# 09_MCU.net
KiCad netlist of a schematic drawn in Altium Designer
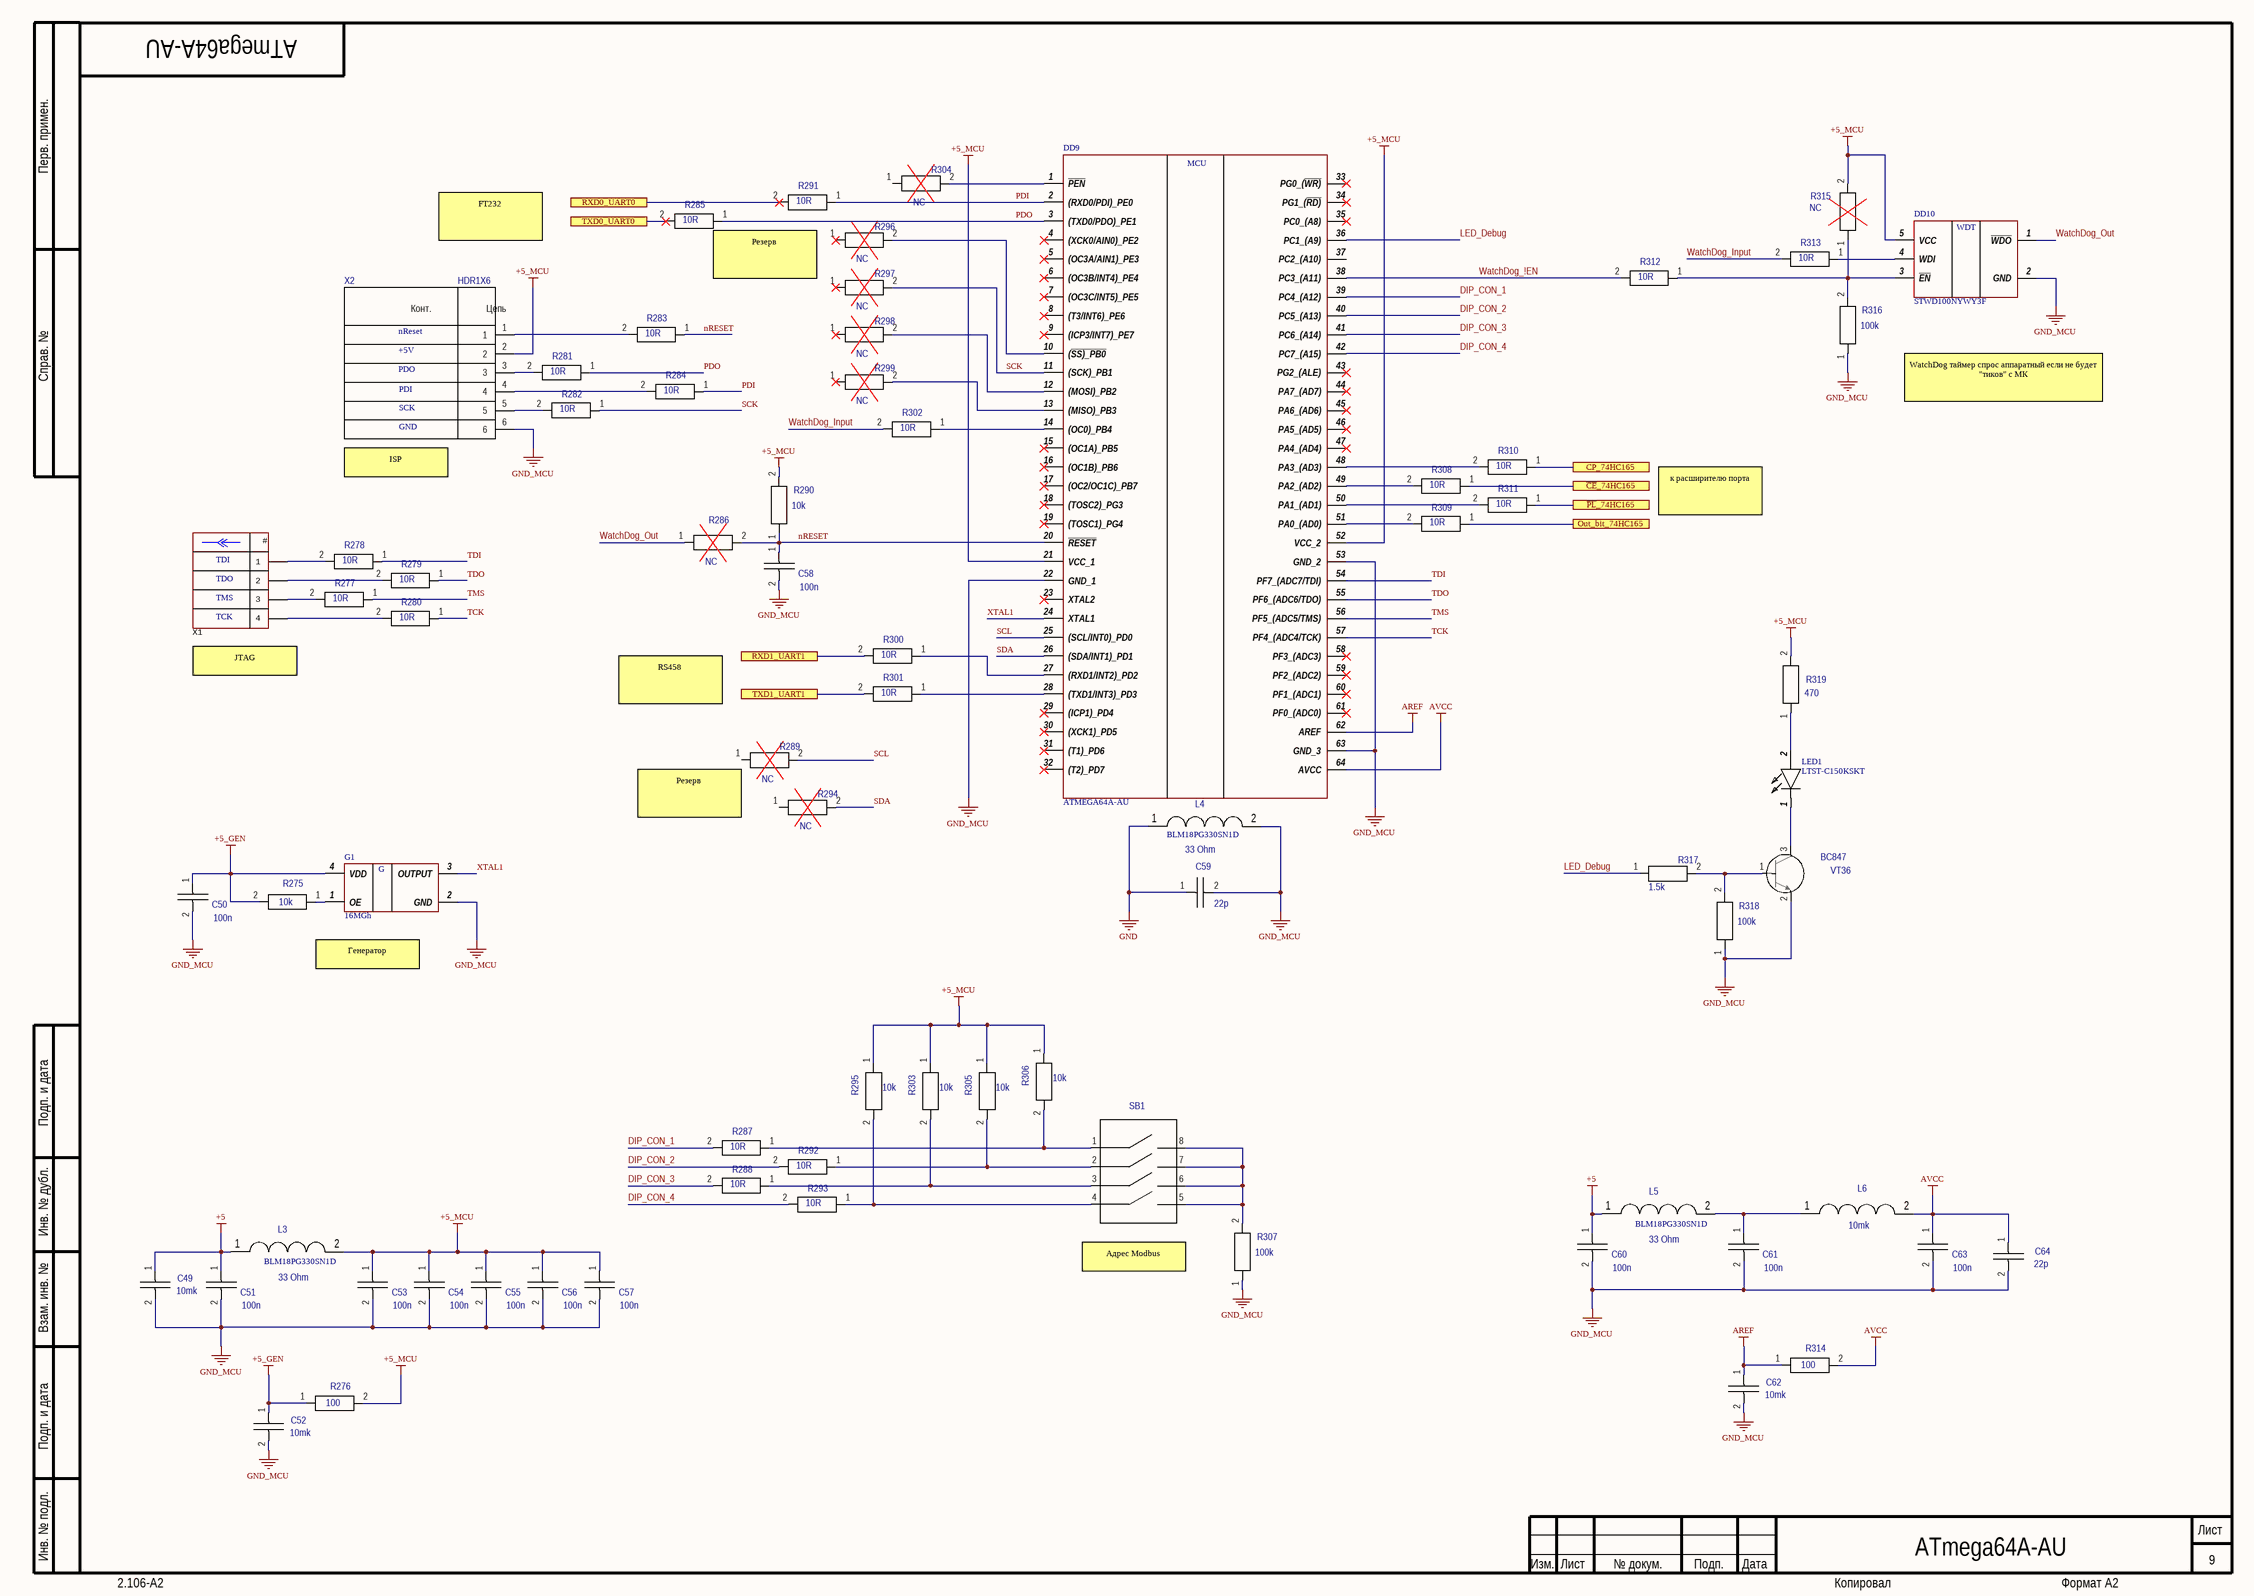
[diagram p0: 09_MCU.SchDoc]

(export (version "E")
  (design (tool "Eeschema 10.0.6"))
  (components
    (comp (ref "C49")
      (value "10mk")
      (footprint "C1206")
      (fields
        (field (name "PART NUMBER") "GRM31CR71E106KA12L")
        (field (name "TOLERANCE") "±10%")
        (field (name "MANUFACTURER") "Murata Manufacturing")
      )
      (libsource (lib "AccessLibrary") (part "Capacitor"))
    )
    (comp (ref "C50")
      (value "100n")
      (footprint "C0603")
      (fields
        (field (name "PART NUMBER") "GRM188R71C104KA01D")
        (field (name "TOLERANCE") "±10%")
        (field (name "MANUFACTURER") "Murata Manufacturing")
      )
      (libsource (lib "AccessLibrary") (part "Capacitor"))
    )
    (comp (ref "C51")
      (value "100n")
      (footprint "C0603")
      (fields
        (field (name "PART NUMBER") "GRM188R71C104KA01D")
        (field (name "TOLERANCE") "±10%")
        (field (name "MANUFACTURER") "Murata Manufacturing")
      )
      (libsource (lib "AccessLibrary") (part "Capacitor"))
    )
    (comp (ref "C52")
      (value "10mk")
      (footprint "C1206")
      (fields
        (field (name "PART NUMBER") "GRM31CR71E106KA12L")
        (field (name "TOLERANCE") "±10%")
        (field (name "MANUFACTURER") "Murata Manufacturing")
      )
      (libsource (lib "AccessLibrary") (part "Capacitor"))
    )
    (comp (ref "C53")
      (value "100n")
      (footprint "C0603")
      (fields
        (field (name "PART NUMBER") "GRM188R71C104KA01D")
        (field (name "TOLERANCE") "±10%")
        (field (name "MANUFACTURER") "Murata Manufacturing")
      )
      (libsource (lib "AccessLibrary") (part "Capacitor"))
    )
    (comp (ref "C54")
      (value "100n")
      (footprint "C0603")
      (fields
        (field (name "PART NUMBER") "GRM188R71C104KA01D")
        (field (name "TOLERANCE") "±10%")
        (field (name "MANUFACTURER") "Murata Manufacturing")
      )
      (libsource (lib "AccessLibrary") (part "Capacitor"))
    )
    (comp (ref "C55")
      (value "100n")
      (footprint "C0603")
      (fields
        (field (name "PART NUMBER") "GRM188R71C104KA01D")
        (field (name "TOLERANCE") "±10%")
        (field (name "MANUFACTURER") "Murata Manufacturing")
      )
      (libsource (lib "AccessLibrary") (part "Capacitor"))
    )
    (comp (ref "C56")
      (value "100n")
      (footprint "C0603")
      (fields
        (field (name "PART NUMBER") "GRM188R71C104KA01D")
        (field (name "TOLERANCE") "±10%")
        (field (name "MANUFACTURER") "Murata Manufacturing")
      )
      (libsource (lib "AccessLibrary") (part "Capacitor"))
    )
    (comp (ref "C57")
      (value "100n")
      (footprint "C0603")
      (fields
        (field (name "PART NUMBER") "GRM188R71C104KA01D")
        (field (name "TOLERANCE") "±10%")
        (field (name "MANUFACTURER") "Murata Manufacturing")
      )
      (libsource (lib "AccessLibrary") (part "Capacitor"))
    )
    (comp (ref "C58")
      (value "100n")
      (footprint "C0603")
      (fields
        (field (name "PART NUMBER") "GRM188R71C104KA01D")
        (field (name "TOLERANCE") "±10%")
        (field (name "MANUFACTURER") "Murata Manufacturing")
      )
      (libsource (lib "AccessLibrary") (part "Capacitor"))
    )
    (comp (ref "C59")
      (value "22p")
      (footprint "C0603")
      (fields
        (field (name "PART NUMBER") "GRM1885C1H220JA01D")
        (field (name "TOLERANCE") "±5%")
        (field (name "MANUFACTURER") "Murata Manufacturing")
      )
      (libsource (lib "AccessLibrary") (part "Capacitor"))
    )
    (comp (ref "C60")
      (value "100n")
      (footprint "C0603")
      (fields
        (field (name "PART NUMBER") "GRM188R71C104KA01D")
        (field (name "TOLERANCE") "±10%")
        (field (name "MANUFACTURER") "Murata Manufacturing")
      )
      (libsource (lib "AccessLibrary") (part "Capacitor"))
    )
    (comp (ref "C61")
      (value "100n")
      (footprint "C0603")
      (fields
        (field (name "PART NUMBER") "GRM188R71C104KA01D")
        (field (name "TOLERANCE") "±10%")
        (field (name "MANUFACTURER") "Murata Manufacturing")
      )
      (libsource (lib "AccessLibrary") (part "Capacitor"))
    )
    (comp (ref "C62")
      (value "10mk")
      (footprint "C1206")
      (fields
        (field (name "PART NUMBER") "GRM31CR71E106KA12L")
        (field (name "TOLERANCE") "±10%")
        (field (name "MANUFACTURER") "Murata Manufacturing")
      )
      (libsource (lib "AccessLibrary") (part "Capacitor"))
    )
    (comp (ref "C63")
      (value "100n")
      (footprint "C0603")
      (fields
        (field (name "PART NUMBER") "GRM188R71C104KA01D")
        (field (name "TOLERANCE") "±10%")
        (field (name "MANUFACTURER") "Murata Manufacturing")
      )
      (libsource (lib "AccessLibrary") (part "Capacitor"))
    )
    (comp (ref "C64")
      (value "22p")
      (footprint "C0603")
      (fields
        (field (name "PART NUMBER") "GRM1885C1H220JA01D")
        (field (name "TOLERANCE") "±5%")
        (field (name "MANUFACTURER") "Murata Manufacturing")
      )
      (libsource (lib "AccessLibrary") (part "Capacitor"))
    )
    (comp (ref "DD9")
      (value "ATMEGA64A-AU")
      (footprint "board:QFP80P1600X1600X120-64N")
      (description "Integrated Circuit")
      (fields (field (name "MOUSER PART NUMBER") "556-ATMEGA64A-AU"))
      (libsource (lib "board") (part "ATMEGA64A-AU"))
    )
    (comp (ref "DD10")
      (value "STWD100NYWY3F")
      (footprint "board:SOT95P280X145-5N")
      (description "Integrated Circuit")
      (fields (field (name "MOUSER PART NUMBER") "511-STWD100NYWY3F"))
      (libsource (lib "board") (part "STWD100NYWY3F"))
    )
    (comp (ref "G1")
      (value "16MGh")
      (footprint "board:CSX750FBC14745600T")
      (fields (field (name "MANUFACTURER_PART_NUMBER") "CSX-750FCC"))
      (libsource (lib "board") (part "CSX-750FCC"))
    )
    (comp (ref "L3")
      (value "BLM18PG330SN1D")
      (footprint "INDC1608N")
      (fields (field (name "ALTIUM_VALUE") "33 Ohm"))
      (libsource (lib "AccessLibrary") (part "Inductance"))
    )
    (comp (ref "L4")
      (value "BLM18PG330SN1D")
      (footprint "INDC1608N")
      (fields (field (name "ALTIUM_VALUE") "33 Ohm"))
      (libsource (lib "AccessLibrary") (part "Inductance"))
    )
    (comp (ref "L5")
      (value "BLM18PG330SN1D")
      (footprint "INDC1608N")
      (fields (field (name "ALTIUM_VALUE") "33 Ohm"))
      (libsource (lib "AccessLibrary") (part "Inductance"))
    )
    (comp (ref "L6")
      (value "10mk")
      (footprint "INDC4532AN")
      (fields
        (field (name "PART NUMBER") "B82432-A1103-K")
        (field (name "TOLERANCE") "±10%")
        (field (name "MANUFACTURER") "Epcos")
      )
      (libsource (lib "AccessLibrary") (part "Inductance"))
    )
    (comp (ref "LED1")
      (value "LTST-C150KSKT")
      (footprint "board:LEDC3216X110N")
      (description "LED")
      (fields (field (name "MOUSER PART NUMBER") "859-LTST-C150KSKT"))
      (libsource (lib "board") (part "LTST-C150KSKT"))
    )
    (comp (ref "R275")
      (value "10k")
      (footprint "RESC1608N")
      (fields
        (field (name "PART NUMBER") "RC0603FK-0710KL")
        (field (name "TOLERANCE") "±1%")
        (field (name "MANUFACTURER") "Тайвань")
      )
      (libsource (lib "AccessLibrary") (part "Resistor"))
    )
    (comp (ref "R276")
      (value "100")
      (footprint "RESC1608N")
      (fields
        (field (name "PART NUMBER") "RC0603FK-07100RL")
        (field (name "TOLERANCE") "±1%")
        (field (name "MANUFACTURER") "Тайвань")
      )
      (libsource (lib "AccessLibrary") (part "Resistor"))
    )
    (comp (ref "R277")
      (value "10R")
      (footprint "RESC1608N")
      (fields
        (field (name "PART NUMBER") "RC0603FR-0710RL")
        (field (name "TOLERANCE") "±1%")
        (field (name "MANUFACTURER") "Тайвань")
      )
      (libsource (lib "AccessLibrary") (part "Resistor"))
    )
    (comp (ref "R278")
      (value "10R")
      (footprint "RESC1608N")
      (fields
        (field (name "PART NUMBER") "RC0603FR-0710RL")
        (field (name "TOLERANCE") "±1%")
        (field (name "MANUFACTURER") "Тайвань")
      )
      (libsource (lib "AccessLibrary") (part "Resistor"))
    )
    (comp (ref "R279")
      (value "10R")
      (footprint "RESC1608N")
      (fields
        (field (name "PART NUMBER") "RC0603FR-0710RL")
        (field (name "TOLERANCE") "±1%")
        (field (name "MANUFACTURER") "Тайвань")
      )
      (libsource (lib "AccessLibrary") (part "Resistor"))
    )
    (comp (ref "R280")
      (value "10R")
      (footprint "RESC1608N")
      (fields
        (field (name "PART NUMBER") "RC0603FR-0710RL")
        (field (name "TOLERANCE") "±1%")
        (field (name "MANUFACTURER") "Тайвань")
      )
      (libsource (lib "AccessLibrary") (part "Resistor"))
    )
    (comp (ref "R281")
      (value "10R")
      (footprint "RESC1608N")
      (fields
        (field (name "PART NUMBER") "RC0603FR-0710RL")
        (field (name "TOLERANCE") "±1%")
        (field (name "MANUFACTURER") "Тайвань")
      )
      (libsource (lib "AccessLibrary") (part "Resistor"))
    )
    (comp (ref "R282")
      (value "10R")
      (footprint "RESC1608N")
      (fields
        (field (name "PART NUMBER") "RC0603FR-0710RL")
        (field (name "TOLERANCE") "±1%")
        (field (name "MANUFACTURER") "Тайвань")
      )
      (libsource (lib "AccessLibrary") (part "Resistor"))
    )
    (comp (ref "R283")
      (value "10R")
      (footprint "RESC1608N")
      (fields
        (field (name "PART NUMBER") "RC0603FR-0710RL")
        (field (name "TOLERANCE") "±1%")
        (field (name "MANUFACTURER") "Тайвань")
      )
      (libsource (lib "AccessLibrary") (part "Resistor"))
    )
    (comp (ref "R284")
      (value "10R")
      (footprint "RESC1608N")
      (fields
        (field (name "PART NUMBER") "RC0603FR-0710RL")
        (field (name "TOLERANCE") "±1%")
        (field (name "MANUFACTURER") "Тайвань")
      )
      (libsource (lib "AccessLibrary") (part "Resistor"))
    )
    (comp (ref "R285")
      (value "10R")
      (footprint "RESC1608N")
      (fields
        (field (name "PART NUMBER") "RC0603FR-0710RL")
        (field (name "TOLERANCE") "±1%")
        (field (name "MANUFACTURER") "Тайвань")
      )
      (libsource (lib "AccessLibrary") (part "Resistor"))
    )
    (comp (ref "R286")
      (value "NC")
      (footprint "RESC1608N")
      (fields (field (name "PART NUMBER") "0603_NC") (field (name "Comment") "R0603"))
      (libsource (lib "AccessLibrary") (part "Resistor_NC"))
    )
    (comp (ref "R287")
      (value "10R")
      (footprint "RESC1608N")
      (fields
        (field (name "PART NUMBER") "RC0603FR-0710RL")
        (field (name "TOLERANCE") "±1%")
        (field (name "MANUFACTURER") "Тайвань")
      )
      (libsource (lib "AccessLibrary") (part "Resistor"))
    )
    (comp (ref "R288")
      (value "10R")
      (footprint "RESC1608N")
      (fields
        (field (name "PART NUMBER") "RC0603FR-0710RL")
        (field (name "TOLERANCE") "±1%")
        (field (name "MANUFACTURER") "Тайвань")
      )
      (libsource (lib "AccessLibrary") (part "Resistor"))
    )
    (comp (ref "R289")
      (value "NC")
      (footprint "RESC1608N")
      (fields (field (name "PART NUMBER") "0603_NC") (field (name "Comment") "R0603"))
      (libsource (lib "AccessLibrary") (part "Resistor_NC"))
    )
    (comp (ref "R290")
      (value "10k")
      (footprint "RESC1608N")
      (fields
        (field (name "PART NUMBER") "RC0603FK-0710KL")
        (field (name "TOLERANCE") "±1%")
        (field (name "MANUFACTURER") "Тайвань")
      )
      (libsource (lib "AccessLibrary") (part "Resistor"))
    )
    (comp (ref "R291")
      (value "10R")
      (footprint "RESC1608N")
      (fields
        (field (name "PART NUMBER") "RC0603FR-0710RL")
        (field (name "TOLERANCE") "±1%")
        (field (name "MANUFACTURER") "Тайвань")
      )
      (libsource (lib "AccessLibrary") (part "Resistor"))
    )
    (comp (ref "R292")
      (value "10R")
      (footprint "RESC1608N")
      (fields
        (field (name "PART NUMBER") "RC0603FR-0710RL")
        (field (name "TOLERANCE") "±1%")
        (field (name "MANUFACTURER") "Тайвань")
      )
      (libsource (lib "AccessLibrary") (part "Resistor"))
    )
    (comp (ref "R293")
      (value "10R")
      (footprint "RESC1608N")
      (fields
        (field (name "PART NUMBER") "RC0603FR-0710RL")
        (field (name "TOLERANCE") "±1%")
        (field (name "MANUFACTURER") "Тайвань")
      )
      (libsource (lib "AccessLibrary") (part "Resistor"))
    )
    (comp (ref "R294")
      (value "NC")
      (footprint "RESC1608N")
      (fields (field (name "PART NUMBER") "0603_NC") (field (name "Comment") "R0603"))
      (libsource (lib "AccessLibrary") (part "Resistor_NC"))
    )
    (comp (ref "R295")
      (value "10k")
      (footprint "RESC1608N")
      (fields
        (field (name "PART NUMBER") "RC0603FK-0710KL")
        (field (name "TOLERANCE") "±1%")
        (field (name "MANUFACTURER") "Тайвань")
      )
      (libsource (lib "AccessLibrary") (part "Resistor"))
    )
    (comp (ref "R296")
      (value "NC")
      (footprint "RESC1608N")
      (fields (field (name "PART NUMBER") "0603_NC") (field (name "Comment") "R0603"))
      (libsource (lib "AccessLibrary") (part "Resistor_NC"))
    )
    (comp (ref "R297")
      (value "NC")
      (footprint "RESC1608N")
      (fields (field (name "PART NUMBER") "0603_NC") (field (name "Comment") "R0603"))
      (libsource (lib "AccessLibrary") (part "Resistor_NC"))
    )
    (comp (ref "R298")
      (value "NC")
      (footprint "RESC1608N")
      (fields (field (name "PART NUMBER") "0603_NC") (field (name "Comment") "R0603"))
      (libsource (lib "AccessLibrary") (part "Resistor_NC"))
    )
    (comp (ref "R299")
      (value "NC")
      (footprint "RESC1608N")
      (fields (field (name "PART NUMBER") "0603_NC") (field (name "Comment") "R0603"))
      (libsource (lib "AccessLibrary") (part "Resistor_NC"))
    )
    (comp (ref "R300")
      (value "10R")
      (footprint "RESC1608N")
      (fields
        (field (name "PART NUMBER") "RC0603FR-0710RL")
        (field (name "TOLERANCE") "±1%")
        (field (name "MANUFACTURER") "Тайвань")
      )
      (libsource (lib "AccessLibrary") (part "Resistor"))
    )
    (comp (ref "R301")
      (value "10R")
      (footprint "RESC1608N")
      (fields
        (field (name "PART NUMBER") "RC0603FR-0710RL")
        (field (name "TOLERANCE") "±1%")
        (field (name "MANUFACTURER") "Тайвань")
      )
      (libsource (lib "AccessLibrary") (part "Resistor"))
    )
    (comp (ref "R302")
      (value "10R")
      (footprint "RESC1608N")
      (fields
        (field (name "PART NUMBER") "RC0603FR-0710RL")
        (field (name "TOLERANCE") "±1%")
        (field (name "MANUFACTURER") "Тайвань")
      )
      (libsource (lib "AccessLibrary") (part "Resistor"))
    )
    (comp (ref "R303")
      (value "10k")
      (footprint "RESC1608N")
      (fields
        (field (name "PART NUMBER") "RC0603FK-0710KL")
        (field (name "TOLERANCE") "±1%")
        (field (name "MANUFACTURER") "Тайвань")
      )
      (libsource (lib "AccessLibrary") (part "Resistor"))
    )
    (comp (ref "R304")
      (value "NC")
      (footprint "RESC1608N")
      (fields (field (name "PART NUMBER") "0603_NC") (field (name "Comment") "R0603"))
      (libsource (lib "AccessLibrary") (part "Resistor_NC"))
    )
    (comp (ref "R305")
      (value "10k")
      (footprint "RESC1608N")
      (fields
        (field (name "PART NUMBER") "RC0603FK-0710KL")
        (field (name "TOLERANCE") "±1%")
        (field (name "MANUFACTURER") "Тайвань")
      )
      (libsource (lib "AccessLibrary") (part "Resistor"))
    )
    (comp (ref "R306")
      (value "10k")
      (footprint "RESC1608N")
      (fields
        (field (name "PART NUMBER") "RC0603FK-0710KL")
        (field (name "TOLERANCE") "±1%")
        (field (name "MANUFACTURER") "Тайвань")
      )
      (libsource (lib "AccessLibrary") (part "Resistor"))
    )
    (comp (ref "R307")
      (value "100k")
      (footprint "RESC1608N")
      (fields
        (field (name "PART NUMBER") "RC0603FK-07100KL")
        (field (name "TOLERANCE") "±1%")
        (field (name "MANUFACTURER") "Тайвань")
      )
      (libsource (lib "AccessLibrary") (part "Resistor"))
    )
    (comp (ref "R308")
      (value "10R")
      (footprint "RESC1608N")
      (fields
        (field (name "PART NUMBER") "RC0603FR-0710RL")
        (field (name "TOLERANCE") "±1%")
        (field (name "MANUFACTURER") "Тайвань")
      )
      (libsource (lib "AccessLibrary") (part "Resistor"))
    )
    (comp (ref "R309")
      (value "10R")
      (footprint "RESC1608N")
      (fields
        (field (name "PART NUMBER") "RC0603FR-0710RL")
        (field (name "TOLERANCE") "±1%")
        (field (name "MANUFACTURER") "Тайвань")
      )
      (libsource (lib "AccessLibrary") (part "Resistor"))
    )
    (comp (ref "R310")
      (value "10R")
      (footprint "RESC1608N")
      (fields
        (field (name "PART NUMBER") "RC0603FR-0710RL")
        (field (name "TOLERANCE") "±1%")
        (field (name "MANUFACTURER") "Тайвань")
      )
      (libsource (lib "AccessLibrary") (part "Resistor"))
    )
    (comp (ref "R311")
      (value "10R")
      (footprint "RESC1608N")
      (fields
        (field (name "PART NUMBER") "RC0603FR-0710RL")
        (field (name "TOLERANCE") "±1%")
        (field (name "MANUFACTURER") "Тайвань")
      )
      (libsource (lib "AccessLibrary") (part "Resistor"))
    )
    (comp (ref "R312")
      (value "10R")
      (footprint "RESC1608N")
      (fields
        (field (name "PART NUMBER") "RC0603FR-0710RL")
        (field (name "TOLERANCE") "±1%")
        (field (name "MANUFACTURER") "Тайвань")
      )
      (libsource (lib "AccessLibrary") (part "Resistor"))
    )
    (comp (ref "R313")
      (value "10R")
      (footprint "RESC1608N")
      (fields
        (field (name "PART NUMBER") "RC0603FR-0710RL")
        (field (name "TOLERANCE") "±1%")
        (field (name "MANUFACTURER") "Тайвань")
      )
      (libsource (lib "AccessLibrary") (part "Resistor"))
    )
    (comp (ref "R314")
      (value "100")
      (footprint "RESC1608N")
      (fields
        (field (name "PART NUMBER") "RC0603FK-07100RL")
        (field (name "TOLERANCE") "±1%")
        (field (name "MANUFACTURER") "Тайвань")
      )
      (libsource (lib "AccessLibrary") (part "Resistor"))
    )
    (comp (ref "R315")
      (value "NC")
      (footprint "RESC1608N")
      (fields (field (name "PART NUMBER") "0603_NC") (field (name "Comment") "R0603"))
      (libsource (lib "AccessLibrary") (part "Resistor_NC"))
    )
    (comp (ref "R316")
      (value "100k")
      (footprint "RESC1608N")
      (fields
        (field (name "PART NUMBER") "RC0603FK-07100KL")
        (field (name "TOLERANCE") "±1%")
        (field (name "MANUFACTURER") "Тайвань")
      )
      (libsource (lib "AccessLibrary") (part "Resistor"))
    )
    (comp (ref "R317")
      (value "1.5k")
      (footprint "RESC1608N")
      (fields
        (field (name "PART NUMBER") "RC0603FK-071K5L")
        (field (name "TOLERANCE") "±1%")
        (field (name "MANUFACTURER") "Тайвань")
      )
      (libsource (lib "AccessLibrary") (part "Resistor"))
    )
    (comp (ref "R318")
      (value "100k")
      (footprint "RESC1608N")
      (fields
        (field (name "PART NUMBER") "RC0603FK-07100KL")
        (field (name "TOLERANCE") "±1%")
        (field (name "MANUFACTURER") "Тайвань")
      )
      (libsource (lib "AccessLibrary") (part "Resistor"))
    )
    (comp (ref "R319")
      (value "470")
      (footprint "RESC1608N")
      (fields
        (field (name "PART NUMBER") "RC0603FK-07470RL")
        (field (name "TOLERANCE") "±1%")
        (field (name "MANUFACTURER") "Тайвань")
      )
      (libsource (lib "AccessLibrary") (part "Resistor"))
    )
    (comp (ref "SB1")
      (value "DS1040-04RN")
      (footprint "Dip_4pin")
      (libsource (lib "AccessLibrary") (part "Dip_4pin"))
    )
    (comp (ref "VT36")
      (value "BC847")
      (footprint "SOT23-3N")
      (fields (field (name "COM") "BC847") (field (name "MANUFACTURER") "NXP Semiconductor"))
      (libsource (lib "AccessLibrary") (part "Transistor_npn_1b-2e-3c"))
    )
    (comp (ref "X1")
      (value "~")
      (footprint "board:CON: PBS-4")
      (fields
        (field (name "MANUFACTURER") "Connfly")
        (field (name "VALUEMANUFACTURERPARTNUMBER") "Connector, 4pin, 2.54mm, 500VAC, 3A")
        (field (name "PARTNUMBER") "PBS-4")
      )
      (libsource (lib "board") (part "PBS-4"))
    )
    (comp (ref "X2")
      (value "HDR1X6")
      (footprint "HDR1X6")
      (fields (field (name "MANUFACTURER") "Dinkle Enterprise"))
      (libsource (lib "AccessLibrary") (part "HDR1X6"))
    )
  )
  (nets
    (net (code "1") (name "+5") (class "Default")
      (node (ref "C49") (pin "1") (pinfunction "1_1") (pintype "passive"))
      (node (ref "C51") (pin "1") (pinfunction "1_1") (pintype "passive"))
      (node (ref "C60") (pin "1") (pinfunction "1_1") (pintype "passive"))
      (node (ref "L3") (pin "1") (pinfunction "1_1") (pintype "passive"))
      (node (ref "L5") (pin "1") (pinfunction "1_1") (pintype "passive"))
    )
    (net (code "2") (name "+5_GEN") (class "Default")
      (node (ref "C50") (pin "1") (pinfunction "1_1") (pintype "passive"))
      (node (ref "C52") (pin "1") (pinfunction "1_1") (pintype "passive"))
      (node (ref "G1") (pin "4") (pinfunction "VDD_4") (pintype "passive"))
      (node (ref "R275") (pin "2") (pinfunction "2_2") (pintype "passive"))
      (node (ref "R276") (pin "1") (pinfunction "1_1") (pintype "passive"))
    )
    (net (code "3") (name "+5_MCU") (class "Default")
      (node (ref "C53") (pin "1") (pinfunction "1_1") (pintype "passive"))
      (node (ref "C54") (pin "1") (pinfunction "1_1") (pintype "passive"))
      (node (ref "C55") (pin "1") (pinfunction "1_1") (pintype "passive"))
      (node (ref "C56") (pin "1") (pinfunction "1_1") (pintype "passive"))
      (node (ref "C57") (pin "1") (pinfunction "1_1") (pintype "passive"))
      (node (ref "DD10") (pin "5") (pinfunction "VCC_5") (pintype "passive"))
      (node (ref "DD9") (pin "21") (pinfunction "VCC_1_21") (pintype "passive"))
      (node (ref "DD9") (pin "52") (pinfunction "VCC_2_52") (pintype "passive"))
      (node (ref "L3") (pin "2") (pinfunction "2_2") (pintype "passive"))
      (node (ref "R276") (pin "2") (pinfunction "2_2") (pintype "passive"))
      (node (ref "R290") (pin "2") (pinfunction "2_2") (pintype "passive"))
      (node (ref "R295") (pin "1") (pinfunction "1_1") (pintype "passive"))
      (node (ref "R303") (pin "1") (pinfunction "1_1") (pintype "passive"))
      (node (ref "R305") (pin "1") (pinfunction "1_1") (pintype "passive"))
      (node (ref "R306") (pin "1") (pinfunction "1_1") (pintype "passive"))
      (node (ref "R315") (pin "2") (pinfunction "2_2") (pintype "passive"))
      (node (ref "R319") (pin "2") (pinfunction "2_2") (pintype "passive"))
      (node (ref "X2") (pin "2") (pinfunction "2_2") (pintype "passive"))
    )
    (net (code "4") (name "/CP_74HC165") (class "Default")
      (node (ref "R310") (pin "1") (pinfunction "1_1") (pintype "passive"))
    )
    (net (code "5") (name "/DIP_CON_1") (class "Default")
      (node (ref "DD9") (pin "39") (pinfunction "PC4_(A12)_39") (pintype "passive"))
      (node (ref "R287") (pin "2") (pinfunction "2_2") (pintype "passive"))
    )
    (net (code "6") (name "/DIP_CON_2") (class "Default")
      (node (ref "DD9") (pin "40") (pinfunction "PC5_(A13)_40") (pintype "passive"))
      (node (ref "R292") (pin "2") (pinfunction "2_2") (pintype "passive"))
    )
    (net (code "7") (name "/DIP_CON_3") (class "Default")
      (node (ref "DD9") (pin "41") (pinfunction "PC6_(A14)_41") (pintype "passive"))
      (node (ref "R288") (pin "2") (pinfunction "2_2") (pintype "passive"))
    )
    (net (code "8") (name "/DIP_CON_4") (class "Default")
      (node (ref "DD9") (pin "42") (pinfunction "PC7_(A15)_42") (pintype "passive"))
      (node (ref "R293") (pin "2") (pinfunction "2_2") (pintype "passive"))
    )
    (net (code "9") (name "/LED_Debug") (class "Default")
      (node (ref "DD9") (pin "36") (pinfunction "PC1_(A9)_36") (pintype "passive"))
      (node (ref "R317") (pin "1") (pinfunction "1_1") (pintype "passive"))
    )
    (net (code "10") (name "/Out_bit_74HC165") (class "Default")
      (node (ref "R309") (pin "1") (pinfunction "1_1") (pintype "passive"))
    )
    (net (code "11") (name "/PDI") (class "Default")
      (node (ref "DD9") (pin "2") (pinfunction "(RXD0/PDI)_PE0_2") (pintype "passive"))
      (node (ref "R284") (pin "1") (pinfunction "1_1") (pintype "passive"))
      (node (ref "R291") (pin "1") (pinfunction "1_1") (pintype "passive"))
    )
    (net (code "12") (name "/PDO") (class "Default")
      (node (ref "DD9") (pin "3") (pinfunction "(TXD0/PDO)_PE1_3") (pintype "passive"))
      (node (ref "R281") (pin "1") (pinfunction "1_1") (pintype "passive"))
      (node (ref "R285") (pin "1") (pinfunction "1_1") (pintype "passive"))
    )
    (net (code "13") (name "/RXD0_UART0") (class "Default")
      (node (ref "R291") (pin "2") (pinfunction "2_2") (pintype "passive+no_connect"))
    )
    (net (code "14") (name "/RXD1_UART1") (class "Default")
      (node (ref "R300") (pin "2") (pinfunction "2_2") (pintype "passive"))
    )
    (net (code "15") (name "/SCK") (class "Default")
      (node (ref "DD9") (pin "11") (pinfunction "(SCK)_PB1_11") (pintype "passive"))
      (node (ref "R282") (pin "1") (pinfunction "1_1") (pintype "passive"))
      (node (ref "R297") (pin "2") (pinfunction "2_2") (pintype "passive"))
    )
    (net (code "16") (name "/SCL") (class "Default")
      (node (ref "DD9") (pin "25") (pinfunction "(SCL/INT0)_PD0_25") (pintype "passive"))
      (node (ref "R289") (pin "2") (pinfunction "2_2") (pintype "passive"))
    )
    (net (code "17") (name "/SDA") (class "Default")
      (node (ref "DD9") (pin "26") (pinfunction "(SDA/INT1)_PD1_26") (pintype "passive"))
      (node (ref "R294") (pin "2") (pinfunction "2_2") (pintype "passive"))
    )
    (net (code "18") (name "/TCK") (class "Default")
      (node (ref "DD9") (pin "57") (pinfunction "PF4_(ADC4/TCK)_57") (pintype "passive"))
      (node (ref "R280") (pin "1") (pinfunction "1_1") (pintype "passive"))
    )
    (net (code "19") (name "/TDI") (class "Default")
      (node (ref "DD9") (pin "54") (pinfunction "PF7_(ADC7/TDI)_54") (pintype "passive"))
      (node (ref "R278") (pin "1") (pinfunction "1_1") (pintype "passive"))
    )
    (net (code "20") (name "/TDO") (class "Default")
      (node (ref "DD9") (pin "55") (pinfunction "PF6_(ADC6/TDO)_55") (pintype "passive"))
      (node (ref "R279") (pin "1") (pinfunction "1_1") (pintype "passive"))
    )
    (net (code "21") (name "/TMS") (class "Default")
      (node (ref "DD9") (pin "56") (pinfunction "PF5_(ADC5/TMS)_56") (pintype "passive"))
      (node (ref "R277") (pin "1") (pinfunction "1_1") (pintype "passive"))
    )
    (net (code "22") (name "/TXD0_UART0") (class "Default")
      (node (ref "R285") (pin "2") (pinfunction "2_2") (pintype "passive+no_connect"))
    )
    (net (code "23") (name "/TXD1_UART1") (class "Default")
      (node (ref "R301") (pin "2") (pinfunction "2_2") (pintype "passive"))
    )
    (net (code "24") (name "/WatchDog_!EN") (class "Default")
      (node (ref "DD9") (pin "38") (pinfunction "PC3_(A11)_38") (pintype "passive"))
      (node (ref "R312") (pin "2") (pinfunction "2_2") (pintype "passive"))
    )
    (net (code "25") (name "/WatchDog_Input") (class "Default")
      (node (ref "R302") (pin "2") (pinfunction "2_2") (pintype "passive"))
      (node (ref "R313") (pin "2") (pinfunction "2_2") (pintype "passive"))
    )
    (net (code "26") (name "/WatchDog_Out") (class "Default")
      (node (ref "DD10") (pin "1") (pinfunction "~{WDO}_1") (pintype "passive"))
      (node (ref "R286") (pin "1") (pinfunction "1_1") (pintype "passive"))
    )
    (net (code "27") (name "/XTAL1") (class "Default")
      (node (ref "DD9") (pin "24") (pinfunction "XTAL1_24") (pintype "passive"))
      (node (ref "G1") (pin "3") (pinfunction "OUTPUT_3") (pintype "passive"))
    )
    (net (code "28") (name "/nRESET") (class "Default")
      (node (ref "C58") (pin "1") (pinfunction "1_1") (pintype "passive"))
      (node (ref "DD9") (pin "20") (pinfunction "~{RESET}_20") (pintype "passive"))
      (node (ref "R283") (pin "1") (pinfunction "1_1") (pintype "passive"))
      (node (ref "R286") (pin "2") (pinfunction "2_2") (pintype "passive"))
      (node (ref "R290") (pin "1") (pinfunction "1_1") (pintype "passive"))
    )
    (net (code "29") (name "/~{CE}_74HC165") (class "Default")
      (node (ref "R308") (pin "1") (pinfunction "1_1") (pintype "passive"))
    )
    (net (code "30") (name "/~{PL}_74HC165") (class "Default")
      (node (ref "R311") (pin "1") (pinfunction "1_1") (pintype "passive"))
    )
    (net (code "31") (name "AREF") (class "Default")
      (node (ref "C62") (pin "1") (pinfunction "1_1") (pintype "passive"))
      (node (ref "DD9") (pin "62") (pinfunction "AREF_62") (pintype "passive"))
      (node (ref "R314") (pin "1") (pinfunction "1_1") (pintype "passive"))
    )
    (net (code "32") (name "AVCC") (class "Default")
      (node (ref "C63") (pin "1") (pinfunction "1_1") (pintype "passive"))
      (node (ref "C64") (pin "1") (pinfunction "1_1") (pintype "passive"))
      (node (ref "DD9") (pin "64") (pinfunction "AVCC_64") (pintype "passive"))
      (node (ref "L6") (pin "2") (pinfunction "2_2") (pintype "passive"))
      (node (ref "R314") (pin "2") (pinfunction "2_2") (pintype "passive"))
    )
    (net (code "33") (name "GND") (class "Default")
      (node (ref "C59") (pin "1") (pinfunction "1_1") (pintype "passive"))
      (node (ref "L4") (pin "1") (pinfunction "1_1") (pintype "passive"))
    )
    (net (code "34") (name "GND_MCU") (class "Default")
      (node (ref "C49") (pin "2") (pinfunction "2_2") (pintype "passive"))
      (node (ref "C50") (pin "2") (pinfunction "2_2") (pintype "passive"))
      (node (ref "C51") (pin "2") (pinfunction "2_2") (pintype "passive"))
      (node (ref "C52") (pin "2") (pinfunction "2_2") (pintype "passive"))
      (node (ref "C53") (pin "2") (pinfunction "2_2") (pintype "passive"))
      (node (ref "C54") (pin "2") (pinfunction "2_2") (pintype "passive"))
      (node (ref "C55") (pin "2") (pinfunction "2_2") (pintype "passive"))
      (node (ref "C56") (pin "2") (pinfunction "2_2") (pintype "passive"))
      (node (ref "C57") (pin "2") (pinfunction "2_2") (pintype "passive"))
      (node (ref "C58") (pin "2") (pinfunction "2_2") (pintype "passive"))
      (node (ref "C59") (pin "2") (pinfunction "2_2") (pintype "passive"))
      (node (ref "C60") (pin "2") (pinfunction "2_2") (pintype "passive"))
      (node (ref "C61") (pin "2") (pinfunction "2_2") (pintype "passive"))
      (node (ref "C62") (pin "2") (pinfunction "2_2") (pintype "passive"))
      (node (ref "C63") (pin "2") (pinfunction "2_2") (pintype "passive"))
      (node (ref "C64") (pin "2") (pinfunction "2_2") (pintype "passive"))
      (node (ref "DD10") (pin "2") (pinfunction "GND_2") (pintype "passive"))
      (node (ref "DD9") (pin "22") (pinfunction "GND_1_22") (pintype "passive"))
      (node (ref "DD9") (pin "53") (pinfunction "GND_2_53") (pintype "passive"))
      (node (ref "DD9") (pin "63") (pinfunction "GND_3_63") (pintype "passive"))
      (node (ref "G1") (pin "2") (pinfunction "GND_2") (pintype "passive"))
      (node (ref "L4") (pin "2") (pinfunction "2_2") (pintype "passive"))
      (node (ref "R307") (pin "1") (pinfunction "1_1") (pintype "passive"))
      (node (ref "R316") (pin "1") (pinfunction "1_1") (pintype "passive"))
      (node (ref "R318") (pin "1") (pinfunction "1_1") (pintype "passive"))
      (node (ref "VT36") (pin "2") (pinfunction "2_2") (pintype "passive"))
      (node (ref "X2") (pin "6") (pinfunction "6_6") (pintype "passive"))
    )
    (net (code "35") (name "Net-(C61-Pad1)") (class "Default")
      (node (ref "C61") (pin "1") (pinfunction "1_1") (pintype "passive"))
      (node (ref "L5") (pin "2") (pinfunction "2_2") (pintype "passive"))
      (node (ref "L6") (pin "1") (pinfunction "1_1") (pintype "passive"))
    )
    (net (code "36") (name "Net-(DD9-(MISO)_PB3)") (class "Default")
      (node (ref "DD9") (pin "13") (pinfunction "(MISO)_PB3_13") (pintype "passive"))
      (node (ref "R299") (pin "2") (pinfunction "2_2") (pintype "passive"))
    )
    (net (code "37") (name "Net-(DD9-(MOSI)_PB2)") (class "Default")
      (node (ref "DD9") (pin "12") (pinfunction "(MOSI)_PB2_12") (pintype "passive"))
      (node (ref "R298") (pin "2") (pinfunction "2_2") (pintype "passive"))
    )
    (net (code "38") (name "Net-(DD9-(OC0)_PB4)") (class "Default")
      (node (ref "DD9") (pin "14") (pinfunction "(OC0)_PB4_14") (pintype "passive"))
      (node (ref "R302") (pin "1") (pinfunction "1_1") (pintype "passive"))
    )
    (net (code "39") (name "Net-(DD9-(RXD1{slash}INT2)_PD2)") (class "Default")
      (node (ref "DD9") (pin "27") (pinfunction "(RXD1/INT2)_PD2_27") (pintype "passive"))
      (node (ref "R300") (pin "1") (pinfunction "1_1") (pintype "passive"))
    )
    (net (code "40") (name "Net-(DD9-(TXD1{slash}INT3)_PD3)") (class "Default")
      (node (ref "DD9") (pin "28") (pinfunction "(TXD1/INT3)_PD3_28") (pintype "passive"))
      (node (ref "R301") (pin "1") (pinfunction "1_1") (pintype "passive"))
    )
    (net (code "41") (name "Net-(DD9-(~{SS)_PB0})") (class "Default")
      (node (ref "DD9") (pin "10") (pinfunction "(~{SS)_PB0}_10") (pintype "passive"))
      (node (ref "R296") (pin "2") (pinfunction "2_2") (pintype "passive"))
    )
    (net (code "42") (name "Net-(DD9-PA0_(AD0))") (class "Default")
      (node (ref "DD9") (pin "51") (pinfunction "PA0_(AD0)_51") (pintype "passive"))
      (node (ref "R309") (pin "2") (pinfunction "2_2") (pintype "passive"))
    )
    (net (code "43") (name "Net-(DD9-PA1_(AD1))") (class "Default")
      (node (ref "DD9") (pin "50") (pinfunction "PA1_(AD1)_50") (pintype "passive"))
      (node (ref "R311") (pin "2") (pinfunction "2_2") (pintype "passive"))
    )
    (net (code "44") (name "Net-(DD9-PA2_(AD2))") (class "Default")
      (node (ref "DD9") (pin "49") (pinfunction "PA2_(AD2)_49") (pintype "passive"))
      (node (ref "R308") (pin "2") (pinfunction "2_2") (pintype "passive"))
    )
    (net (code "45") (name "Net-(DD9-PA3_(AD3))") (class "Default")
      (node (ref "DD9") (pin "48") (pinfunction "PA3_(AD3)_48") (pintype "passive"))
      (node (ref "R310") (pin "2") (pinfunction "2_2") (pintype "passive"))
    )
    (net (code "46") (name "Net-(DD9-~{PEN})") (class "Default")
      (node (ref "DD9") (pin "1") (pinfunction "~{PEN}_1") (pintype "passive"))
      (node (ref "R304") (pin "2") (pinfunction "2_2") (pintype "passive"))
    )
    (net (code "47") (name "Net-(DD10-WDI)") (class "Default")
      (node (ref "DD10") (pin "4") (pinfunction "WDI_4") (pintype "passive"))
      (node (ref "R313") (pin "1") (pinfunction "1_1") (pintype "passive"))
    )
    (net (code "48") (name "Net-(DD10-~{EN})") (class "Default")
      (node (ref "DD10") (pin "3") (pinfunction "~{EN}_3") (pintype "passive"))
      (node (ref "R312") (pin "1") (pinfunction "1_1") (pintype "passive"))
      (node (ref "R315") (pin "1") (pinfunction "1_1") (pintype "passive"))
      (node (ref "R316") (pin "2") (pinfunction "2_2") (pintype "passive"))
    )
    (net (code "49") (name "Net-(G1-OE)") (class "Default")
      (node (ref "G1") (pin "1") (pinfunction "OE_1") (pintype "passive"))
      (node (ref "R275") (pin "1") (pinfunction "1_1") (pintype "passive"))
    )
    (net (code "50") (name "Net-(LED1-A)") (class "Default")
      (node (ref "LED1") (pin "2") (pinfunction "A_2") (pintype "passive"))
      (node (ref "R319") (pin "1") (pinfunction "1_1") (pintype "passive"))
    )
    (net (code "51") (name "Net-(LED1-K)") (class "Default")
      (node (ref "LED1") (pin "1") (pinfunction "K_1") (pintype "passive"))
      (node (ref "VT36") (pin "3") (pinfunction "3_3") (pintype "passive"))
    )
    (net (code "52") (name "Net-(R277-Pad2)") (class "Default")
      (node (ref "R277") (pin "2") (pinfunction "2_2") (pintype "passive"))
      (node (ref "X1") (pin "3") (pinfunction "3_3") (pintype "power_in"))
    )
    (net (code "53") (name "Net-(R278-Pad2)") (class "Default")
      (node (ref "R278") (pin "2") (pinfunction "2_2") (pintype "passive"))
      (node (ref "X1") (pin "1") (pinfunction "1_1") (pintype "passive"))
    )
    (net (code "54") (name "Net-(R279-Pad2)") (class "Default")
      (node (ref "R279") (pin "2") (pinfunction "2_2") (pintype "passive"))
      (node (ref "X1") (pin "2") (pinfunction "2_2") (pintype "passive"))
    )
    (net (code "55") (name "Net-(R280-Pad2)") (class "Default")
      (node (ref "R280") (pin "2") (pinfunction "2_2") (pintype "passive"))
      (node (ref "X1") (pin "4") (pinfunction "4_4") (pintype "power_in"))
    )
    (net (code "56") (name "Net-(R281-Pad2)") (class "Default")
      (node (ref "R281") (pin "2") (pinfunction "2_2") (pintype "passive"))
      (node (ref "X2") (pin "3") (pinfunction "3_3") (pintype "passive"))
    )
    (net (code "57") (name "Net-(R282-Pad2)") (class "Default")
      (node (ref "R282") (pin "2") (pinfunction "2_2") (pintype "passive"))
      (node (ref "X2") (pin "5") (pinfunction "5_5") (pintype "passive"))
    )
    (net (code "58") (name "Net-(R283-Pad2)") (class "Default")
      (node (ref "R283") (pin "2") (pinfunction "2_2") (pintype "passive"))
      (node (ref "X2") (pin "1") (pinfunction "1_1") (pintype "passive"))
    )
    (net (code "59") (name "Net-(R284-Pad2)") (class "Default")
      (node (ref "R284") (pin "2") (pinfunction "2_2") (pintype "passive"))
      (node (ref "X2") (pin "4") (pinfunction "4_4") (pintype "passive"))
    )
    (net (code "60") (name "Net-(R287-Pad1)") (class "Default")
      (node (ref "R287") (pin "1") (pinfunction "1_1") (pintype "passive"))
      (node (ref "R306") (pin "2") (pinfunction "2_2") (pintype "passive"))
      (node (ref "SB1") (pin "1") (pinfunction "1_1") (pintype "passive"))
    )
    (net (code "61") (name "Net-(R288-Pad1)") (class "Default")
      (node (ref "R288") (pin "1") (pinfunction "1_1") (pintype "passive"))
      (node (ref "R303") (pin "2") (pinfunction "2_2") (pintype "passive"))
      (node (ref "SB1") (pin "3") (pinfunction "3_3") (pintype "passive"))
    )
    (net (code "62") (name "Net-(R292-Pad1)") (class "Default")
      (node (ref "R292") (pin "1") (pinfunction "1_1") (pintype "passive"))
      (node (ref "R305") (pin "2") (pinfunction "2_2") (pintype "passive"))
      (node (ref "SB1") (pin "2") (pinfunction "2_2") (pintype "passive"))
    )
    (net (code "63") (name "Net-(R293-Pad1)") (class "Default")
      (node (ref "R293") (pin "1") (pinfunction "1_1") (pintype "passive"))
      (node (ref "R295") (pin "2") (pinfunction "2_2") (pintype "passive"))
      (node (ref "SB1") (pin "4") (pinfunction "4_4") (pintype "passive"))
    )
    (net (code "64") (name "Net-(R307-Pad2)") (class "Default")
      (node (ref "R307") (pin "2") (pinfunction "2_2") (pintype "passive"))
      (node (ref "SB1") (pin "5") (pinfunction "5_5") (pintype "passive"))
      (node (ref "SB1") (pin "6") (pinfunction "6_6") (pintype "passive"))
      (node (ref "SB1") (pin "7") (pinfunction "7_7") (pintype "passive"))
      (node (ref "SB1") (pin "8") (pinfunction "8_8") (pintype "passive"))
    )
    (net (code "65") (name "Net-(R317-Pad2)") (class "Default")
      (node (ref "R317") (pin "2") (pinfunction "2_2") (pintype "passive"))
      (node (ref "R318") (pin "2") (pinfunction "2_2") (pintype "passive"))
      (node (ref "VT36") (pin "1") (pinfunction "1_1") (pintype "passive"))
    )
    (net (code "66") (name "unconnected-(DD9-(ICP1)_PD4-Pad29)") (class "Default")
      (node (ref "DD9") (pin "29") (pinfunction "(ICP1)_PD4_29") (pintype "passive+no_connect"))
    )
    (net (code "67") (name "unconnected-(DD9-(ICP3{slash}INT7)_PE7-Pad9)") (class "Default")
      (node (ref "DD9") (pin "9") (pinfunction "(ICP3/INT7)_PE7_9") (pintype "passive+no_connect"))
    )
    (net (code "68") (name "unconnected-(DD9-(OC1A)_PB5-Pad15)") (class "Default")
      (node (ref "DD9") (pin "15") (pinfunction "(OC1A)_PB5_15") (pintype "passive+no_connect"))
    )
    (net (code "69") (name "unconnected-(DD9-(OC1B)_PB6-Pad16)") (class "Default")
      (node (ref "DD9") (pin "16") (pinfunction "(OC1B)_PB6_16") (pintype "passive+no_connect"))
    )
    (net (code "70") (name "unconnected-(DD9-(OC2{slash}OC1C)_PB7-Pad17)") (class "Default")
      (node (ref "DD9") (pin "17") (pinfunction "(OC2/OC1C)_PB7_17") (pintype "passive+no_connect"))
    )
    (net (code "71") (name "unconnected-(DD9-(OC3A{slash}AIN1)_PE3-Pad5)") (class "Default")
      (node (ref "DD9") (pin "5") (pinfunction "(OC3A/AIN1)_PE3_5") (pintype "passive+no_connect"))
    )
    (net (code "72") (name "unconnected-(DD9-(OC3B{slash}INT4)_PE4-Pad6)") (class "Default")
      (node (ref "DD9") (pin "6") (pinfunction "(OC3B/INT4)_PE4_6") (pintype "passive+no_connect"))
    )
    (net (code "73") (name "unconnected-(DD9-(OC3C{slash}INT5)_PE5-Pad7)") (class "Default")
      (node (ref "DD9") (pin "7") (pinfunction "(OC3C/INT5)_PE5_7") (pintype "passive+no_connect"))
    )
    (net (code "74") (name "unconnected-(DD9-(T1)_PD6-Pad31)") (class "Default")
      (node (ref "DD9") (pin "31") (pinfunction "(T1)_PD6_31") (pintype "passive+no_connect"))
    )
    (net (code "75") (name "unconnected-(DD9-(T2)_PD7-Pad32)") (class "Default")
      (node (ref "DD9") (pin "32") (pinfunction "(T2)_PD7_32") (pintype "passive+no_connect"))
    )
    (net (code "76") (name "unconnected-(DD9-(T3{slash}INT6)_PE6-Pad8)") (class "Default")
      (node (ref "DD9") (pin "8") (pinfunction "(T3/INT6)_PE6_8") (pintype "passive+no_connect"))
    )
    (net (code "77") (name "unconnected-(DD9-(TOSC1)_PG4-Pad19)") (class "Default")
      (node (ref "DD9") (pin "19") (pinfunction "(TOSC1)_PG4_19") (pintype "passive+no_connect"))
    )
    (net (code "78") (name "unconnected-(DD9-(TOSC2)_PG3-Pad18)") (class "Default")
      (node (ref "DD9") (pin "18") (pinfunction "(TOSC2)_PG3_18") (pintype "passive+no_connect"))
    )
    (net (code "79") (name "unconnected-(DD9-(XCK0{slash}AIN0)_PE2-Pad4)") (class "Default")
      (node (ref "DD9") (pin "4") (pinfunction "(XCK0/AIN0)_PE2_4") (pintype "passive+no_connect"))
    )
    (net (code "80") (name "unconnected-(DD9-(XCK1)_PD5-Pad30)") (class "Default")
      (node (ref "DD9") (pin "30") (pinfunction "(XCK1)_PD5_30") (pintype "passive+no_connect"))
    )
    (net (code "81") (name "unconnected-(DD9-PA4_(AD4)-Pad47)") (class "Default")
      (node (ref "DD9") (pin "47") (pinfunction "PA4_(AD4)_47") (pintype "passive+no_connect"))
    )
    (net (code "82") (name "unconnected-(DD9-PA5_(AD5)-Pad46)") (class "Default")
      (node (ref "DD9") (pin "46") (pinfunction "PA5_(AD5)_46") (pintype "passive+no_connect"))
    )
    (net (code "83") (name "unconnected-(DD9-PA6_(AD6)-Pad45)") (class "Default")
      (node (ref "DD9") (pin "45") (pinfunction "PA6_(AD6)_45") (pintype "passive+no_connect"))
    )
    (net (code "84") (name "unconnected-(DD9-PA7_(AD7)-Pad44)") (class "Default")
      (node (ref "DD9") (pin "44") (pinfunction "PA7_(AD7)_44") (pintype "passive+no_connect"))
    )
    (net (code "85") (name "unconnected-(DD9-PC0_(A8)-Pad35)") (class "Default")
      (node (ref "DD9") (pin "35") (pinfunction "PC0_(A8)_35") (pintype "passive+no_connect"))
    )
    (net (code "86") (name "unconnected-(DD9-PC2_(A10)-Pad37)") (class "Default")
      (node (ref "DD9") (pin "37") (pinfunction "PC2_(A10)_37") (pintype "passive"))
    )
    (net (code "87") (name "unconnected-(DD9-PF0_(ADC0)-Pad61)") (class "Default")
      (node (ref "DD9") (pin "61") (pinfunction "PF0_(ADC0)_61") (pintype "passive+no_connect"))
    )
    (net (code "88") (name "unconnected-(DD9-PF1_(ADC1)-Pad60)") (class "Default")
      (node (ref "DD9") (pin "60") (pinfunction "PF1_(ADC1)_60") (pintype "passive+no_connect"))
    )
    (net (code "89") (name "unconnected-(DD9-PF2_(ADC2)-Pad59)") (class "Default")
      (node (ref "DD9") (pin "59") (pinfunction "PF2_(ADC2)_59") (pintype "passive+no_connect"))
    )
    (net (code "90") (name "unconnected-(DD9-PF3_(ADC3)-Pad58)") (class "Default")
      (node (ref "DD9") (pin "58") (pinfunction "PF3_(ADC3)_58") (pintype "passive+no_connect"))
    )
    (net (code "91") (name "unconnected-(DD9-PG0_(~{WR)}-Pad33)") (class "Default")
      (node (ref "DD9") (pin "33") (pinfunction "PG0_(~{WR)}_33") (pintype "passive+no_connect"))
    )
    (net (code "92") (name "unconnected-(DD9-PG1_(~{RD)}-Pad34)") (class "Default")
      (node (ref "DD9") (pin "34") (pinfunction "PG1_(~{RD)}_34") (pintype "passive+no_connect"))
    )
    (net (code "93") (name "unconnected-(DD9-PG2_(ALE)-Pad43)") (class "Default")
      (node (ref "DD9") (pin "43") (pinfunction "PG2_(ALE)_43") (pintype "passive+no_connect"))
    )
    (net (code "94") (name "unconnected-(DD9-XTAL2-Pad23)") (class "Default")
      (node (ref "DD9") (pin "23") (pinfunction "XTAL2_23") (pintype "passive+no_connect"))
    )
    (net (code "95") (name "unconnected-(R289-Pad1)") (class "Default")
      (node (ref "R289") (pin "1") (pinfunction "1_1") (pintype "passive"))
    )
    (net (code "96") (name "unconnected-(R294-Pad1)") (class "Default")
      (node (ref "R294") (pin "1") (pinfunction "1_1") (pintype "passive"))
    )
    (net (code "97") (name "unconnected-(R296-Pad1)") (class "Default")
      (node (ref "R296") (pin "1") (pinfunction "1_1") (pintype "passive+no_connect"))
    )
    (net (code "98") (name "unconnected-(R297-Pad1)") (class "Default")
      (node (ref "R297") (pin "1") (pinfunction "1_1") (pintype "passive+no_connect"))
    )
    (net (code "99") (name "unconnected-(R298-Pad1)") (class "Default")
      (node (ref "R298") (pin "1") (pinfunction "1_1") (pintype "passive+no_connect"))
    )
    (net (code "100") (name "unconnected-(R299-Pad1)") (class "Default")
      (node (ref "R299") (pin "1") (pinfunction "1_1") (pintype "passive+no_connect"))
    )
    (net (code "101") (name "unconnected-(R304-Pad1)") (class "Default")
      (node (ref "R304") (pin "1") (pinfunction "1_1") (pintype "passive"))
    )
  )
)
